# D3R910.net
KiCad netlist of a schematic drawn in Altium Designer
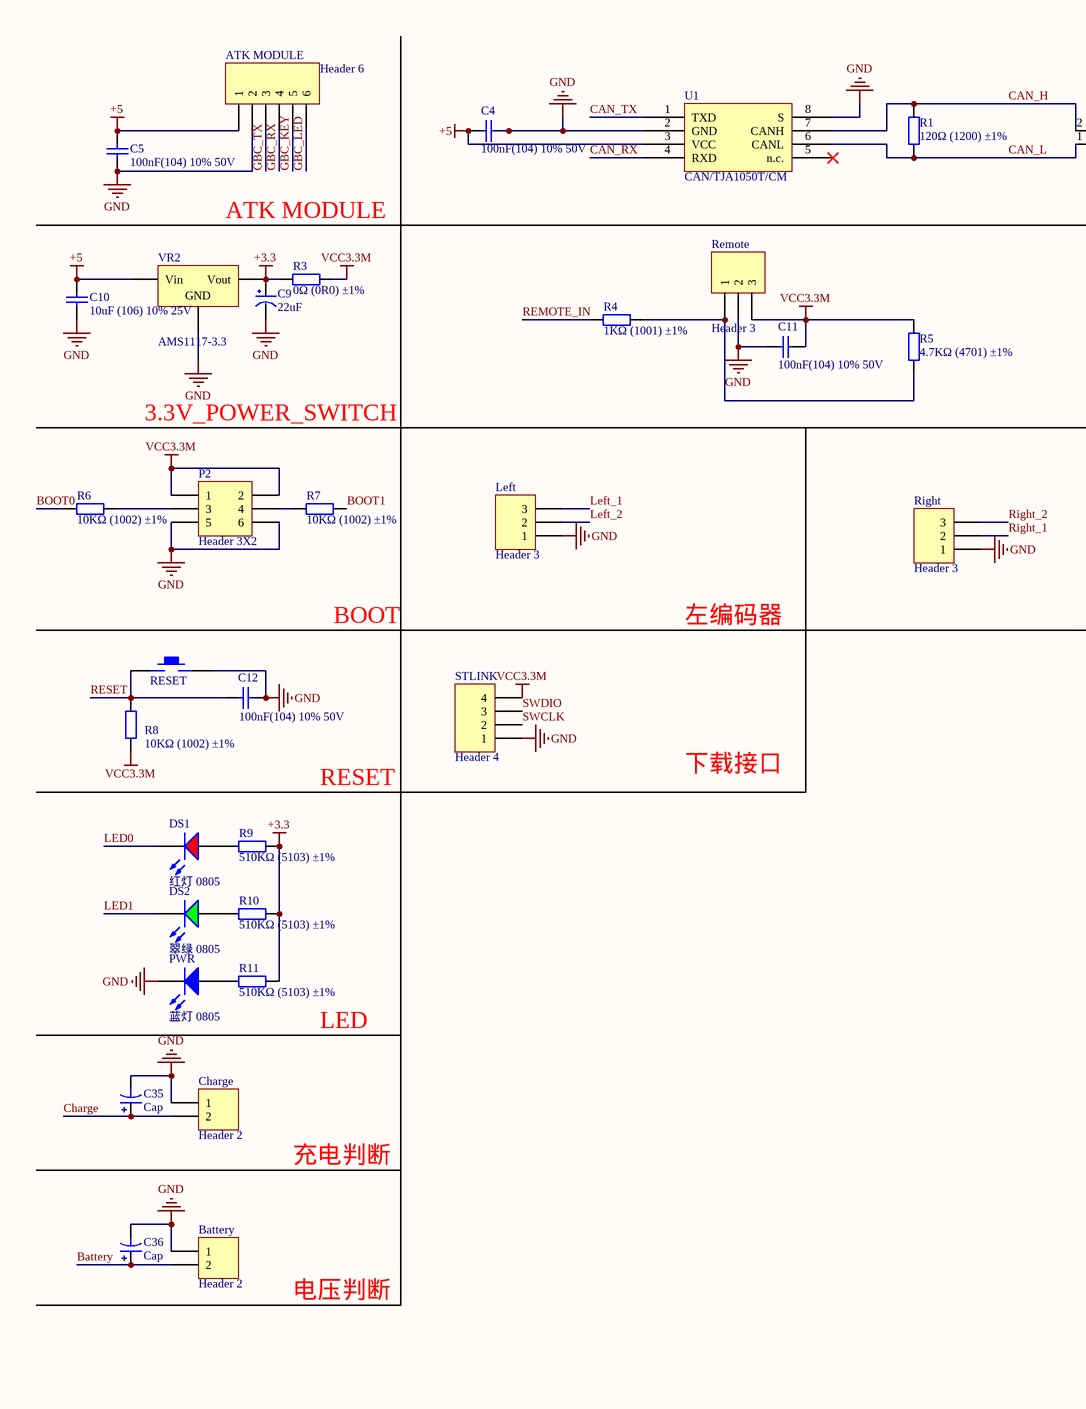
[diagram p0: D3R910.SchDoc, left]
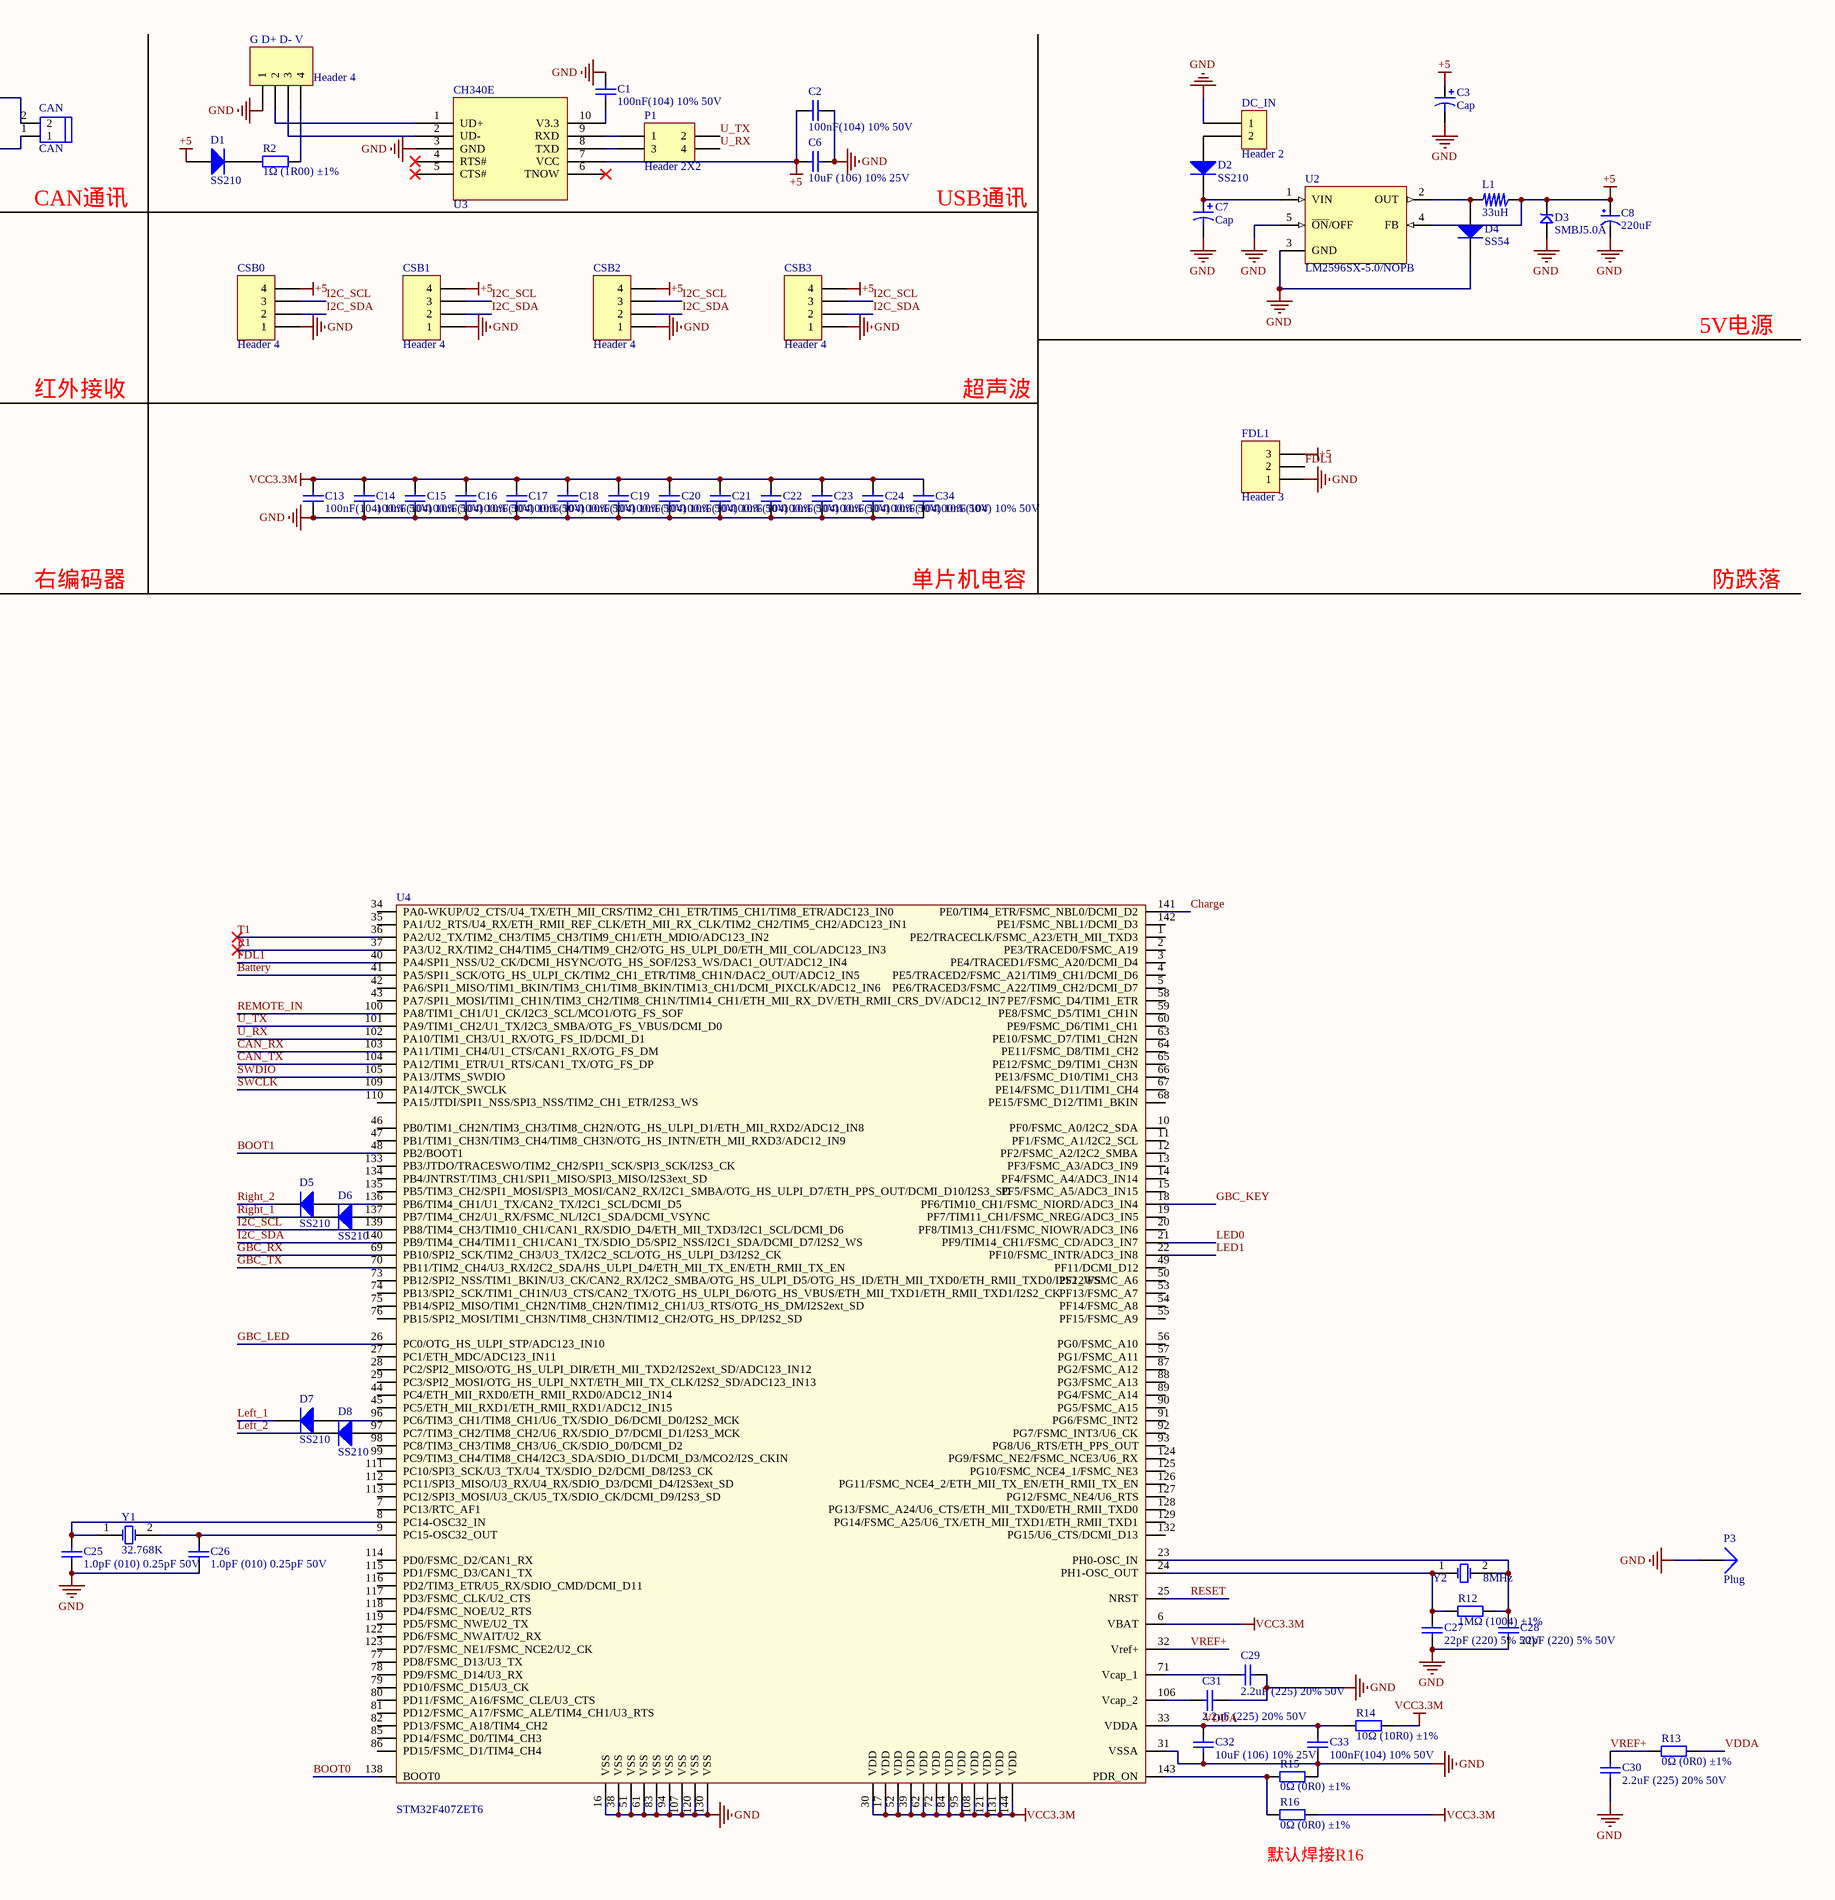
[diagram p1: D3R910.SchDoc, right]

(export (version "E")
  (design (tool "Eeschema 10.0.6"))
  (components
    (comp (ref "ATK MODULE")
      (value "Header 6")
      (footprint "HDR1X6")
      (description "Header, 6-Pin")
      (fields (field (name "PUBLISHER") "Altium Limited"))
      (libsource (lib "Miscellaneous Connectors") (part "Header 6"))
    )
    (comp (ref "Battery")
      (value "Header 2")
      (footprint "HDR1X2")
      (description "Header, 2-Pin")
      (fields (field (name "PUBLISHER") "Altium Limited"))
      (libsource (lib "Miscellaneous Connectors") (part "Header 2"))
    )
    (comp (ref "C1")
      (value "100nF(104) 10% 50V")
      (footprint "LC-0805_C")
      (description "贴片电容")
      (libsource (lib "Miscellaneous Devices LC") (part "0805 100nF(104) 10% 50V"))
    )
    (comp (ref "C2")
      (value "100nF(104) 10% 50V")
      (footprint "LC-0805_C")
      (description "贴片电容")
      (libsource (lib "Miscellaneous Devices LC") (part "0805 100nF(104) 10% 50V"))
    )
    (comp (ref "C3")
      (value "Cap")
      (footprint "CAP-DIP-3.5")
      (description "Cap_DIP")
      (libsource (lib "AD_Chip_Y") (part "Cap_DIP"))
    )
    (comp (ref "C4")
      (value "100nF(104) 10% 50V")
      (footprint "LC-0805_C")
      (description "贴片电容")
      (libsource (lib "Miscellaneous Devices LC") (part "0805 100nF(104) 10% 50V"))
    )
    (comp (ref "C5")
      (value "100nF(104) 10% 50V")
      (footprint "LC-0805_C")
      (description "贴片电容")
      (libsource (lib "Miscellaneous Devices LC") (part "0805 100nF(104) 10% 50V"))
    )
    (comp (ref "C6")
      (value "10uF (106) 10% 25V")
      (footprint "LC-0805_C")
      (description "贴片电容")
      (libsource (lib "Miscellaneous Devices LC") (part "0805 10uF (106) 10% 25V"))
    )
    (comp (ref "C7")
      (value "Cap")
      (footprint "CAP-DIP-3.5")
      (description "Cap_DIP")
      (libsource (lib "AD_Chip_Y") (part "Cap_DIP"))
    )
    (comp (ref "C8")
      (value "220uF")
      (footprint "CC6.56.5")
      (libsource (lib "Explorer STM32F407封装库") (part "CAP"))
    )
    (comp (ref "C9")
      (value "22uF")
      (footprint "CC6.56.5")
      (libsource (lib "Explorer STM32F407封装库") (part "CAP"))
    )
    (comp (ref "C10")
      (value "10uF (106) 10% 25V")
      (footprint "LC-0805_C")
      (description "贴片电容")
      (libsource (lib "Miscellaneous Devices LC") (part "0805 10uF (106) 10% 25V"))
    )
    (comp (ref "C11")
      (value "100nF(104) 10% 50V")
      (footprint "LC-0805_C")
      (description "贴片电容")
      (libsource (lib "Miscellaneous Devices LC") (part "0805 100nF(104) 10% 50V"))
    )
    (comp (ref "C12")
      (value "100nF(104) 10% 50V")
      (footprint "LC-0805_C")
      (description "贴片电容")
      (libsource (lib "Miscellaneous Devices LC") (part "0805 100nF(104) 10% 50V"))
    )
    (comp (ref "C13")
      (value "100nF(104) 10% 50V")
      (footprint "LC-0805_C")
      (description "贴片电容")
      (libsource (lib "Miscellaneous Devices LC") (part "0805 100nF(104) 10% 50V"))
    )
    (comp (ref "C14")
      (value "100nF(104) 10% 50V")
      (footprint "LC-0805_C")
      (description "贴片电容")
      (libsource (lib "Miscellaneous Devices LC") (part "0805 100nF(104) 10% 50V"))
    )
    (comp (ref "C15")
      (value "100nF(104) 10% 50V")
      (footprint "LC-0805_C")
      (description "贴片电容")
      (libsource (lib "Miscellaneous Devices LC") (part "0805 100nF(104) 10% 50V"))
    )
    (comp (ref "C16")
      (value "100nF(104) 10% 50V")
      (footprint "LC-0805_C")
      (description "贴片电容")
      (libsource (lib "Miscellaneous Devices LC") (part "0805 100nF(104) 10% 50V"))
    )
    (comp (ref "C17")
      (value "100nF(104) 10% 50V")
      (footprint "LC-0805_C")
      (description "贴片电容")
      (libsource (lib "Miscellaneous Devices LC") (part "0805 100nF(104) 10% 50V"))
    )
    (comp (ref "C18")
      (value "100nF(104) 10% 50V")
      (footprint "LC-0805_C")
      (description "贴片电容")
      (libsource (lib "Miscellaneous Devices LC") (part "0805 100nF(104) 10% 50V"))
    )
    (comp (ref "C19")
      (value "100nF(104) 10% 50V")
      (footprint "LC-0805_C")
      (description "贴片电容")
      (libsource (lib "Miscellaneous Devices LC") (part "0805 100nF(104) 10% 50V"))
    )
    (comp (ref "C20")
      (value "100nF(104) 10% 50V")
      (footprint "LC-0805_C")
      (description "贴片电容")
      (libsource (lib "Miscellaneous Devices LC") (part "0805 100nF(104) 10% 50V"))
    )
    (comp (ref "C21")
      (value "100nF(104) 10% 50V")
      (footprint "LC-0805_C")
      (description "贴片电容")
      (libsource (lib "Miscellaneous Devices LC") (part "0805 100nF(104) 10% 50V"))
    )
    (comp (ref "C22")
      (value "100nF(104) 10% 50V")
      (footprint "LC-0805_C")
      (description "贴片电容")
      (libsource (lib "Miscellaneous Devices LC") (part "0805 100nF(104) 10% 50V"))
    )
    (comp (ref "C23")
      (value "100nF(104) 10% 50V")
      (footprint "LC-0805_C")
      (description "贴片电容")
      (libsource (lib "Miscellaneous Devices LC") (part "0805 100nF(104) 10% 50V"))
    )
    (comp (ref "C24")
      (value "100nF(104) 10% 50V")
      (footprint "LC-0805_C")
      (description "贴片电容")
      (libsource (lib "Miscellaneous Devices LC") (part "0805 100nF(104) 10% 50V"))
    )
    (comp (ref "C25")
      (value "1.0pF (010) 0.25pF 50V")
      (footprint "LC-0805_C")
      (description "贴片电容")
      (libsource (lib "Miscellaneous Devices LC") (part "0805 1.0pF (010) 0.25pF 50V"))
    )
    (comp (ref "C26")
      (value "1.0pF (010) 0.25pF 50V")
      (footprint "LC-0805_C")
      (description "贴片电容")
      (libsource (lib "Miscellaneous Devices LC") (part "0805 1.0pF (010) 0.25pF 50V"))
    )
    (comp (ref "C27")
      (value "22pF (220) 5% 50V")
      (footprint "LC-0805_C")
      (description "贴片电容")
      (libsource (lib "Miscellaneous Devices LC") (part "0805 22pF (220) 5% 50V"))
    )
    (comp (ref "C28")
      (value "22pF (220) 5% 50V")
      (footprint "LC-0805_C")
      (description "贴片电容")
      (libsource (lib "Miscellaneous Devices LC") (part "0805 22pF (220) 5% 50V"))
    )
    (comp (ref "C29")
      (value "2.2uF (225) 20% 50V")
      (footprint "LC-0805_C")
      (description "贴片电容")
      (libsource (lib "Miscellaneous Devices LC") (part "0805 2.2uF (225) 20% 50V"))
    )
    (comp (ref "C30")
      (value "2.2uF (225) 20% 50V")
      (footprint "LC-0805_C")
      (description "贴片电容")
      (libsource (lib "Miscellaneous Devices LC") (part "0805 2.2uF (225) 20% 50V"))
    )
    (comp (ref "C31")
      (value "2.2uF (225) 20% 50V")
      (footprint "LC-0805_C")
      (description "贴片电容")
      (libsource (lib "Miscellaneous Devices LC") (part "0805 2.2uF (225) 20% 50V"))
    )
    (comp (ref "C32")
      (value "10uF (106) 10% 25V")
      (footprint "LC-0805_C")
      (description "贴片电容")
      (libsource (lib "Miscellaneous Devices LC") (part "0805 10uF (106) 10% 25V"))
    )
    (comp (ref "C33")
      (value "100nF(104) 10% 50V")
      (footprint "LC-0805_C")
      (description "贴片电容")
      (libsource (lib "Miscellaneous Devices LC") (part "0805 100nF(104) 10% 50V"))
    )
    (comp (ref "C34")
      (value "100nF(104) 10% 50V")
      (footprint "LC-0805_C")
      (description "贴片电容")
      (libsource (lib "Miscellaneous Devices LC") (part "0805 100nF(104) 10% 50V"))
    )
    (comp (ref "C35")
      (value "Cap")
      (footprint "CAP-DIP-3.5")
      (description "Cap_DIP")
      (libsource (lib "AD_Chip_Y") (part "Cap_DIP"))
    )
    (comp (ref "C36")
      (value "Cap")
      (footprint "CAP-DIP-3.5")
      (description "Cap_DIP")
      (libsource (lib "AD_Chip_Y") (part "Cap_DIP"))
    )
    (comp (ref "CAN")
      (value "CAN")
      (footprint "HEAD2L-0.8")
      (libsource (lib "Explorer STM32F407封装库") (part "HEAD2"))
    )
    (comp (ref "Charge")
      (value "Header 2")
      (footprint "HDR1X2")
      (description "Header, 2-Pin")
      (fields (field (name "PUBLISHER") "Altium Limited"))
      (libsource (lib "Miscellaneous Connectors") (part "Header 2"))
    )
    (comp (ref "CSB0")
      (value "Header 4")
      (footprint "HDR1X4")
      (description "Header, 4-Pin")
      (fields (field (name "PUBLISHER") "Altium Limited"))
      (libsource (lib "Miscellaneous Connectors") (part "Header 4"))
    )
    (comp (ref "CSB1")
      (value "Header 4")
      (footprint "HDR1X4")
      (description "Header, 4-Pin")
      (fields (field (name "PUBLISHER") "Altium Limited"))
      (libsource (lib "Miscellaneous Connectors") (part "Header 4"))
    )
    (comp (ref "CSB2")
      (value "Header 4")
      (footprint "HDR1X4")
      (description "Header, 4-Pin")
      (fields (field (name "PUBLISHER") "Altium Limited"))
      (libsource (lib "Miscellaneous Connectors") (part "Header 4"))
    )
    (comp (ref "CSB3")
      (value "Header 4")
      (footprint "HDR1X4")
      (description "Header, 4-Pin")
      (fields (field (name "PUBLISHER") "Altium Limited"))
      (libsource (lib "Miscellaneous Connectors") (part "Header 4"))
    )
    (comp (ref "D1")
      (value "SS210")
      (footprint "LC-SMA(DO-214AC)_S1")
      (description "二极管")
      (libsource (lib "Miscellaneous Devices LC") (part "SMA(DO-214AC) SS210"))
    )
    (comp (ref "D2")
      (value "SS210")
      (footprint "LC-SMA(DO-214AC)_S1")
      (description "二极管")
      (libsource (lib "Miscellaneous Devices LC") (part "SMA(DO-214AC) SS210"))
    )
    (comp (ref "D3")
      (value "SMBJ5.0A")
      (footprint "SMBJ")
      (description "TVS")
      (libsource (lib "Explorer STM32F407封装库") (part "SMBJ"))
    )
    (comp (ref "D4")
      (value "SS54")
      (footprint "LC-SMA(DO-214AC)_S1")
      (description "二极管")
      (libsource (lib "Miscellaneous Devices LC") (part "SMA(DO-214AC) SS54"))
    )
    (comp (ref "D5")
      (value "SS210")
      (footprint "LC-SMA(DO-214AC)_S1")
      (description "二极管")
      (libsource (lib "Miscellaneous Devices LC") (part "SMA(DO-214AC) SS210"))
    )
    (comp (ref "D6")
      (value "SS210")
      (footprint "LC-SMA(DO-214AC)_S1")
      (description "二极管")
      (libsource (lib "Miscellaneous Devices LC") (part "SMA(DO-214AC) SS210"))
    )
    (comp (ref "D7")
      (value "SS210")
      (footprint "LC-SMA(DO-214AC)_S1")
      (description "二极管")
      (libsource (lib "Miscellaneous Devices LC") (part "SMA(DO-214AC) SS210"))
    )
    (comp (ref "D8")
      (value "SS210")
      (footprint "LC-SMA(DO-214AC)_S1")
      (description "二极管")
      (libsource (lib "Miscellaneous Devices LC") (part "SMA(DO-214AC) SS210"))
    )
    (comp (ref "DC_IN")
      (value "Header 2")
      (footprint "VH-2A - Circle Hole")
      (description "贴片2p座")
      (libsource (lib "AD_Chip_Y") (part "Header 2"))
    )
    (comp (ref "DS1")
      (value "红灯 0805")
      (footprint "LC-0805_LED_S1")
      (description "发光二极管")
      (libsource (lib "Miscellaneous Devices LC") (part "0805 红灯"))
    )
    (comp (ref "DS2")
      (value "翠绿 0805")
      (footprint "LC-0805_LED_S1")
      (description "发光二极管")
      (libsource (lib "Miscellaneous Devices LC") (part "0805 翠绿"))
    )
    (comp (ref "FDL1")
      (value "Header 3")
      (footprint "HDR1X3")
      (description "Header, 3-Pin")
      (fields (field (name "PUBLISHER") "Altium Limited"))
      (libsource (lib "") (part "Header 3_1"))
    )
    (comp (ref "G D+ D- V")
      (value "Header 4")
      (footprint "HDR1X4")
      (description "Header, 4-Pin")
      (fields (field (name "PUBLISHER") "Altium Limited"))
      (libsource (lib "") (part "Header 4_1"))
    )
    (comp (ref "L1")
      (value "33uH")
      (footprint "L_SOP74")
      (libsource (lib "Explorer STM32F407封装库") (part "L_SOP"))
    )
    (comp (ref "Left")
      (value "Header 3")
      (footprint "HDR1X3")
      (description "Header, 3-Pin")
      (fields (field (name "PUBLISHER") "Altium Limited"))
      (libsource (lib "") (part "Header 3_1"))
    )
    (comp (ref "P1")
      (value "Header 2X2")
      (footprint "HDR2X2")
      (description "Header, 2-Pin, Dual row")
      (fields (field (name "PUBLISHER") "Altium Limited"))
      (libsource (lib "Miscellaneous Connectors") (part "Header 2X2"))
    )
    (comp (ref "P2")
      (value "Header 3X2")
      (footprint "HDR2X3")
      (description "Header, 3-Pin, Dual row")
      (fields (field (name "PUBLISHER") "Altium Limited"))
      (libsource (lib "Miscellaneous Connectors") (part "Header 3X2"))
    )
    (comp (ref "P3")
      (value "Plug")
      (footprint "PIN1")
      (fields (field (name "PUBLISHER") "Altium Limited"))
      (libsource (lib "Miscellaneous Connectors") (part "Plug"))
    )
    (comp (ref "PWR")
      (value "蓝灯 0805")
      (footprint "LC-0805_LED_S1")
      (description "发光二极管")
      (libsource (lib "Miscellaneous Devices LC") (part "0805 蓝灯"))
    )
    (comp (ref "R1")
      (value "120Ω (1200) ±1%")
      (footprint "LC-0805_R")
      (description "贴片电阻")
      (libsource (lib "Miscellaneous Devices LC") (part "0805 120Ω (1200) 1%"))
    )
    (comp (ref "R2")
      (value "1Ω (1R00) ±1%")
      (footprint "LC-0603_R")
      (description "贴片电阻")
      (libsource (lib "Miscellaneous Devices LC") (part "0603 1Ω (1R00) 1%"))
    )
    (comp (ref "R3")
      (value "0Ω (0R0) ±1%")
      (footprint "LC-0603_R")
      (description "贴片电阻")
      (libsource (lib "Miscellaneous Devices LC") (part "0603 0Ω (0R0) 1%"))
    )
    (comp (ref "R4")
      (value "1KΩ (1001) ±1%")
      (footprint "LC-0805_R")
      (description "贴片电阻")
      (libsource (lib "Miscellaneous Devices LC") (part "0805 1KΩ (1001) 1%"))
    )
    (comp (ref "R5")
      (value "4.7KΩ (4701) ±1%")
      (footprint "LC-0805_R")
      (description "贴片电阻")
      (libsource (lib "Miscellaneous Devices LC") (part "0805 4.7KΩ (4701) 1%"))
    )
    (comp (ref "R6")
      (value "10KΩ (1002) ±1%")
      (footprint "LC-0805_R")
      (description "贴片电阻")
      (libsource (lib "") (part "0805 10KΩ (1002) 1%_1"))
    )
    (comp (ref "R7")
      (value "10KΩ (1002) ±1%")
      (footprint "LC-0805_R")
      (description "贴片电阻")
      (libsource (lib "") (part "0805 10KΩ (1002) 1%_1"))
    )
    (comp (ref "R8")
      (value "10KΩ (1002) ±1%")
      (footprint "LC-0805_R")
      (description "贴片电阻")
      (libsource (lib "Miscellaneous Devices LC") (part "0805 10KΩ (1002) 1%"))
    )
    (comp (ref "R9")
      (value "510KΩ (5103) ±1%")
      (footprint "LC-0805_R")
      (description "贴片电阻")
      (libsource (lib "Miscellaneous Devices LC") (part "0805 510KΩ (5103) 1%"))
    )
    (comp (ref "R10")
      (value "510KΩ (5103) ±1%")
      (footprint "LC-0805_R")
      (description "贴片电阻")
      (libsource (lib "Miscellaneous Devices LC") (part "0805 510KΩ (5103) 1%"))
    )
    (comp (ref "R11")
      (value "510KΩ (5103) ±1%")
      (footprint "LC-0805_R")
      (description "贴片电阻")
      (libsource (lib "Miscellaneous Devices LC") (part "0805 510KΩ (5103) 1%"))
    )
    (comp (ref "R12")
      (value "1MΩ (1004) ±1%")
      (footprint "LC-0805_R")
      (description "贴片电阻")
      (libsource (lib "Miscellaneous Devices LC") (part "0805 1MΩ (1004) 1%"))
    )
    (comp (ref "R13")
      (value "0Ω (0R0) ±1%")
      (footprint "LC-0603_R")
      (description "贴片电阻")
      (libsource (lib "Miscellaneous Devices LC") (part "0603 0Ω (0R0) 1%"))
    )
    (comp (ref "R14")
      (value "10Ω (10R0) ±1%")
      (footprint "LC-0805_R")
      (description "贴片电阻")
      (libsource (lib "Miscellaneous Devices LC") (part "0805 10Ω (10R0) 1%"))
    )
    (comp (ref "R15")
      (value "0Ω (0R0) ±1%")
      (footprint "LC-0603_R")
      (description "贴片电阻")
      (libsource (lib "Miscellaneous Devices LC") (part "0603 0Ω (0R0) 1%"))
    )
    (comp (ref "R16")
      (value "0Ω (0R0) ±1%")
      (footprint "LC-0603_R")
      (description "贴片电阻")
      (libsource (lib "Miscellaneous Devices LC") (part "0603 0Ω (0R0) 1%"))
    )
    (comp (ref "Remote")
      (value "Header 3")
      (footprint "HDR1X3")
      (description "Header, 3-Pin")
      (fields (field (name "PUBLISHER") "Altium Limited"))
      (libsource (lib "Miscellaneous Connectors") (part "Header 3"))
    )
    (comp (ref "RESET")
      (value "KEY_M")
      (footprint "KEY_M")
      (libsource (lib "Explorer STM32F407封装库") (part "KEY_M"))
    )
    (comp (ref "Right")
      (value "Header 3")
      (footprint "HDR1X3")
      (description "Header, 3-Pin")
      (fields (field (name "PUBLISHER") "Altium Limited"))
      (libsource (lib "") (part "Header 3_1"))
    )
    (comp (ref "STLINK")
      (value "Header 4")
      (footprint "HDR1X4")
      (description "Header, 4-Pin")
      (fields (field (name "PUBLISHER") "Altium Limited"))
      (libsource (lib "Miscellaneous Connectors") (part "Header 4"))
    )
    (comp (ref "U1")
      (value "CAN/TJA1050T/CM")
      (footprint "LC-SOIC-8_150mil")
      (description "CAN")
      (libsource (lib "Miscellaneous Devices LC") (part "CAN/TJA1050T/CM"))
    )
    (comp (ref "U2")
      (value "LM2596SX-5.0/NOPB")
      (footprint "LC-TO-263-5")
      (description "DC-DC芯片")
      (libsource (lib "Miscellaneous Devices LC") (part "LM2596SX-5.0/NOPB"))
    )
    (comp (ref "U3")
      (value "CH340E")
      (footprint "LC-MSOP-10")
      (description "USB")
      (libsource (lib "AD_Chip_Y") (part "CH340E"))
    )
    (comp (ref "U4")
      (value "STM32F407ZET6")
      (footprint "LQFP144")
      (libsource (lib "Explorer STM32F407封装库") (part "STM32F407ZET6"))
    )
    (comp (ref "VR2")
      (value "AMS1117-3.3")
      (footprint "LC-SOT-223")
      (description "低压差线性稳压(LDO)")
      (libsource (lib "Miscellaneous Devices LC") (part "SOT-223 AMS1117-3.3"))
    )
    (comp (ref "Y1")
      (value "32.768K")
      (footprint "R38")
      (description "Crystal Oscillator")
      (fields (field (name "PUBLISHER") "Altium Limited"))
      (libsource (lib "Miscellaneous Devices") (part "XTAL"))
    )
    (comp (ref "Y2")
      (value "8MHz")
      (footprint "XTAL_US")
      (description "Crystal Oscillator")
      (fields (field (name "PUBLISHER") "Altium Limited"))
      (libsource (lib "Explorer STM32F407封装库") (part "XTAL"))
    )
  )
  (nets
    (net (code "1") (name "+3.3") (class "Default")
      (node (ref "C9") (pin "1") (pinfunction "VCC_1") (pintype "passive"))
      (node (ref "R10") (pin "2") (pinfunction "2_2") (pintype "passive"))
      (node (ref "R11") (pin "2") (pinfunction "2_2") (pintype "passive"))
      (node (ref "R3") (pin "1") (pinfunction "1_1") (pintype "passive"))
      (node (ref "R9") (pin "2") (pinfunction "2_2") (pintype "passive"))
      (node (ref "VR2") (pin "2") (pinfunction "Vout_2") (pintype "passive"))
    )
    (net (code "2") (name "+5") (class "Default")
      (node (ref "ATK MODULE") (pin "1") (pinfunction "1_1") (pintype "passive"))
      (node (ref "C10") (pin "2") (pinfunction "2_2") (pintype "passive"))
      (node (ref "C2") (pin "1") (pinfunction "1_1") (pintype "passive"))
      (node (ref "C3") (pin "1") (pinfunction "1_1") (pintype "passive"))
      (node (ref "C4") (pin "1") (pinfunction "1_1") (pintype "passive"))
      (node (ref "C5") (pin "2") (pinfunction "2_2") (pintype "passive"))
      (node (ref "C6") (pin "1") (pinfunction "1_1") (pintype "passive"))
      (node (ref "C8") (pin "1") (pinfunction "VCC_1") (pintype "passive"))
      (node (ref "CSB0") (pin "4") (pinfunction "4_4") (pintype "passive"))
      (node (ref "CSB1") (pin "4") (pinfunction "4_4") (pintype "passive"))
      (node (ref "CSB2") (pin "4") (pinfunction "4_4") (pintype "passive"))
      (node (ref "CSB3") (pin "4") (pinfunction "4_4") (pintype "passive"))
      (node (ref "D1") (pin "1") (pinfunction "A_1") (pintype "passive"))
      (node (ref "D3") (pin "2") (pintype "passive"))
      (node (ref "FDL1") (pin "3") (pinfunction "3_3") (pintype "passive"))
      (node (ref "L1") (pin "1") (pinfunction "1_1") (pintype "passive"))
      (node (ref "U1") (pin "3") (pinfunction "VCC_3") (pintype "passive"))
      (node (ref "U2") (pin "4") (pinfunction "FB_4") (pintype "input"))
      (node (ref "U3") (pin "7") (pinfunction "VCC_7") (pintype "passive"))
      (node (ref "VR2") (pin "3") (pinfunction "Vin_3") (pintype "passive"))
    )
    (net (code "3") (name "/BOOT0") (class "Default")
      (node (ref "R6") (pin "1") (pinfunction "1_1") (pintype "passive"))
      (node (ref "U4") (pin "138") (pinfunction "BOOT0_138") (pintype "passive"))
    )
    (net (code "4") (name "/BOOT1") (class "Default")
      (node (ref "R7") (pin "2") (pinfunction "2_2") (pintype "passive"))
      (node (ref "U4") (pin "48") (pinfunction "PB2/BOOT1_48") (pintype "passive"))
    )
    (net (code "5") (name "/Battery") (class "Default")
      (node (ref "Battery") (pin "2") (pinfunction "2_2") (pintype "passive"))
      (node (ref "C36") (pin "1") (pinfunction "1_1") (pintype "passive"))
      (node (ref "U4") (pin "41") (pinfunction "PA5/SPI1_SCK/OTG_HS_ULPI_CK/TIM2_CH1_ETR/TIM8_CH1N/DAC2_OUT/ADC12_IN5_41") (pintype "passive"))
    )
    (net (code "6") (name "/CAN_H") (class "Default")
      (node (ref "CAN") (pin "2") (pinfunction "2_2") (pintype "passive"))
      (node (ref "R1") (pin "2") (pinfunction "2_2") (pintype "passive"))
      (node (ref "U1") (pin "7") (pinfunction "CANH_7") (pintype "passive"))
    )
    (net (code "7") (name "/CAN_L") (class "Default")
      (node (ref "CAN") (pin "1") (pinfunction "1_1") (pintype "passive"))
      (node (ref "R1") (pin "1") (pinfunction "1_1") (pintype "passive"))
      (node (ref "U1") (pin "6") (pinfunction "CANL_6") (pintype "passive"))
    )
    (net (code "8") (name "/CAN_RX") (class "Default")
      (node (ref "U1") (pin "4") (pinfunction "RXD_4") (pintype "passive"))
      (node (ref "U4") (pin "103") (pinfunction "PA11/TIM1_CH4/U1_CTS/CAN1_RX/OTG_FS_DM_103") (pintype "passive"))
    )
    (net (code "9") (name "/CAN_TX") (class "Default")
      (node (ref "U1") (pin "1") (pinfunction "TXD_1") (pintype "passive"))
      (node (ref "U4") (pin "104") (pinfunction "PA12/TIM1_ETR/U1_RTS/CAN1_TX/OTG_FS_DP_104") (pintype "passive"))
    )
    (net (code "10") (name "/Charge") (class "Default")
      (node (ref "C35") (pin "1") (pinfunction "1_1") (pintype "passive"))
      (node (ref "Charge") (pin "2") (pinfunction "2_2") (pintype "passive"))
      (node (ref "U4") (pin "141") (pinfunction "PE0/TIM4_ETR/FSMC_NBL0/DCMI_D2_141") (pintype "passive"))
    )
    (net (code "11") (name "/FDL1") (class "Default")
      (node (ref "FDL1") (pin "2") (pinfunction "2_2") (pintype "passive"))
      (node (ref "U4") (pin "40") (pinfunction "PA4/SPI1_NSS/U2_CK/DCMI_HSYNC/OTG_HS_SOF/I2S3_WS/DAC1_OUT/ADC12_IN4_40") (pintype "passive"))
    )
    (net (code "12") (name "/GBC_KEY") (class "Default")
      (node (ref "ATK MODULE") (pin "5") (pinfunction "5_5") (pintype "passive"))
      (node (ref "U4") (pin "18") (pinfunction "PF6/TIM10_CH1/FSMC_NIORD/ADC3_IN4_18") (pintype "passive"))
    )
    (net (code "13") (name "/GBC_LED") (class "Default")
      (node (ref "ATK MODULE") (pin "6") (pinfunction "6_6") (pintype "passive"))
      (node (ref "U4") (pin "26") (pinfunction "PC0/OTG_HS_ULPI_STP/ADC123_IN10_26") (pintype "passive"))
    )
    (net (code "14") (name "/GBC_RX") (class "Default")
      (node (ref "ATK MODULE") (pin "4") (pinfunction "4_4") (pintype "passive"))
      (node (ref "U4") (pin "69") (pinfunction "PB10/SPI2_SCK/TIM2_CH3/U3_TX/I2C2_SCL/OTG_HS_ULPI_D3/I2S2_CK_69") (pintype "passive"))
    )
    (net (code "15") (name "/GBC_TX") (class "Default")
      (node (ref "ATK MODULE") (pin "3") (pinfunction "3_3") (pintype "passive"))
      (node (ref "U4") (pin "70") (pinfunction "PB11/TIM2_CH4/U3_RX/I2C2_SDA/HS_ULPI_D4/ETH_MII_TX_EN/ETH_RMII_TX_EN_70") (pintype "passive"))
    )
    (net (code "16") (name "/I2C_SCL") (class "Default")
      (node (ref "CSB0") (pin "3") (pinfunction "3_3") (pintype "passive"))
      (node (ref "CSB1") (pin "3") (pinfunction "3_3") (pintype "passive"))
      (node (ref "CSB2") (pin "3") (pinfunction "3_3") (pintype "passive"))
      (node (ref "CSB3") (pin "3") (pinfunction "3_3") (pintype "passive"))
      (node (ref "U4") (pin "139") (pinfunction "PB8/TIM4_CH3/TIM10_CH1/CAN1_RX/SDIO_D4/ETH_MII_TXD3/I2C1_SCL/DCMI_D6_139") (pintype "passive"))
    )
    (net (code "17") (name "/I2C_SDA") (class "Default")
      (node (ref "CSB0") (pin "2") (pinfunction "2_2") (pintype "passive"))
      (node (ref "CSB1") (pin "2") (pinfunction "2_2") (pintype "passive"))
      (node (ref "CSB2") (pin "2") (pinfunction "2_2") (pintype "passive"))
      (node (ref "CSB3") (pin "2") (pinfunction "2_2") (pintype "passive"))
      (node (ref "U4") (pin "140") (pinfunction "PB9/TIM4_CH4/TIM11_CH1/CAN1_TX/SDIO_D5/SPI2_NSS/I2C1_SDA/DCMI_D7/I2S2_WS_140") (pintype "passive"))
    )
    (net (code "18") (name "/LED0") (class "Default")
      (node (ref "DS1") (pin "K") (pinfunction "K_K") (pintype "passive"))
      (node (ref "U4") (pin "21") (pinfunction "PF9/TIM14_CH1/FSMC_CD/ADC3_IN7_21") (pintype "passive"))
    )
    (net (code "19") (name "/LED1") (class "Default")
      (node (ref "DS2") (pin "K") (pinfunction "K_K") (pintype "passive"))
      (node (ref "U4") (pin "22") (pinfunction "PF10/FSMC_INTR/ADC3_IN8_22") (pintype "passive"))
    )
    (net (code "20") (name "/Left_1") (class "Default")
      (node (ref "D7") (pin "2") (pinfunction "K_2") (pintype "passive"))
      (node (ref "Left") (pin "3") (pinfunction "3_3") (pintype "passive"))
    )
    (net (code "21") (name "/Left_2") (class "Default")
      (node (ref "D8") (pin "2") (pinfunction "K_2") (pintype "passive"))
      (node (ref "Left") (pin "2") (pinfunction "2_2") (pintype "passive"))
    )
    (net (code "22") (name "/R1") (class "Default")
      (node (ref "U4") (pin "37") (pinfunction "PA3/U2_RX/TIM2_CH4/TIM5_CH4/TIM9_CH2/OTG_HS_ULPI_D0/ETH_MII_COL/ADC123_IN3_37") (pintype "passive+no_connect"))
    )
    (net (code "23") (name "/REMOTE_IN") (class "Default")
      (node (ref "R4") (pin "1") (pinfunction "1_1") (pintype "passive"))
      (node (ref "U4") (pin "100") (pinfunction "PA8/TIM1_CH1/U1_CK/I2C3_SCL/MCO1/OTG_FS_SOF_100") (pintype "passive"))
    )
    (net (code "24") (name "/RESET") (class "Default")
      (node (ref "C12") (pin "2") (pinfunction "2_2") (pintype "passive"))
      (node (ref "R8") (pin "2") (pinfunction "2_2") (pintype "passive"))
      (node (ref "RESET") (pin "1") (pinfunction "1_1") (pintype "passive"))
      (node (ref "U4") (pin "25") (pinfunction "NRST_25") (pintype "passive"))
    )
    (net (code "25") (name "/Right_1") (class "Default")
      (node (ref "D6") (pin "2") (pinfunction "K_2") (pintype "passive"))
      (node (ref "Right") (pin "2") (pinfunction "2_2") (pintype "passive"))
    )
    (net (code "26") (name "/Right_2") (class "Default")
      (node (ref "D5") (pin "2") (pinfunction "K_2") (pintype "passive"))
      (node (ref "Right") (pin "3") (pinfunction "3_3") (pintype "passive"))
    )
    (net (code "27") (name "/SWCLK") (class "Default")
      (node (ref "STLINK") (pin "2") (pinfunction "2_2") (pintype "passive"))
      (node (ref "U4") (pin "109") (pinfunction "PA14/JTCK_SWCLK_109") (pintype "passive"))
    )
    (net (code "28") (name "/SWDIO") (class "Default")
      (node (ref "STLINK") (pin "3") (pinfunction "3_3") (pintype "passive"))
      (node (ref "U4") (pin "105") (pinfunction "PA13/JTMS_SWDIO_105") (pintype "passive"))
    )
    (net (code "29") (name "/T1") (class "Default")
      (node (ref "U4") (pin "36") (pinfunction "PA2/U2_TX/TIM2_CH3/TIM5_CH3/TIM9_CH1/ETH_MDIO/ADC123_IN2_36") (pintype "passive+no_connect"))
    )
    (net (code "30") (name "/U_RX") (class "Default")
      (node (ref "P1") (pin "4") (pinfunction "4_4") (pintype "passive"))
      (node (ref "U4") (pin "102") (pinfunction "PA10/TIM1_CH3/U1_RX/OTG_FS_ID/DCMI_D1_102") (pintype "passive"))
    )
    (net (code "31") (name "/U_TX") (class "Default")
      (node (ref "P1") (pin "2") (pinfunction "2_2") (pintype "passive"))
      (node (ref "U4") (pin "101") (pinfunction "PA9/TIM1_CH2/U1_TX/I2C3_SMBA/OTG_FS_VBUS/DCMI_D0_101") (pintype "passive"))
    )
    (net (code "32") (name "/VDDA") (class "Default")
      (node (ref "C32") (pin "2") (pinfunction "2_2") (pintype "passive"))
      (node (ref "C33") (pin "2") (pinfunction "2_2") (pintype "passive"))
      (node (ref "R13") (pin "2") (pinfunction "2_2") (pintype "passive"))
      (node (ref "R14") (pin "1") (pinfunction "1_1") (pintype "passive"))
      (node (ref "U4") (pin "33") (pinfunction "VDDA_33") (pintype "passive"))
    )
    (net (code "33") (name "/VREF+") (class "Default")
      (node (ref "C30") (pin "2") (pinfunction "2_2") (pintype "passive"))
      (node (ref "R13") (pin "1") (pinfunction "1_1") (pintype "passive"))
      (node (ref "U4") (pin "32") (pinfunction "Vref+_32") (pintype "passive"))
    )
    (net (code "34") (name "GND") (class "Default")
      (node (ref "ATK MODULE") (pin "2") (pinfunction "2_2") (pintype "passive"))
      (node (ref "Battery") (pin "1") (pinfunction "1_1") (pintype "passive"))
      (node (ref "C1") (pin "2") (pinfunction "2_2") (pintype "passive"))
      (node (ref "C10") (pin "1") (pinfunction "1_1") (pintype "passive"))
      (node (ref "C11") (pin "1") (pinfunction "1_1") (pintype "passive"))
      (node (ref "C12") (pin "1") (pinfunction "1_1") (pintype "passive"))
      (node (ref "C13") (pin "2") (pinfunction "2_2") (pintype "passive"))
      (node (ref "C14") (pin "2") (pinfunction "2_2") (pintype "passive"))
      (node (ref "C15") (pin "2") (pinfunction "2_2") (pintype "passive"))
      (node (ref "C16") (pin "2") (pinfunction "2_2") (pintype "passive"))
      (node (ref "C17") (pin "2") (pinfunction "2_2") (pintype "passive"))
      (node (ref "C18") (pin "2") (pinfunction "2_2") (pintype "passive"))
      (node (ref "C19") (pin "2") (pinfunction "2_2") (pintype "passive"))
      (node (ref "C2") (pin "2") (pinfunction "2_2") (pintype "passive"))
      (node (ref "C20") (pin "2") (pinfunction "2_2") (pintype "passive"))
      (node (ref "C21") (pin "2") (pinfunction "2_2") (pintype "passive"))
      (node (ref "C22") (pin "2") (pinfunction "2_2") (pintype "passive"))
      (node (ref "C23") (pin "2") (pinfunction "2_2") (pintype "passive"))
      (node (ref "C24") (pin "2") (pinfunction "2_2") (pintype "passive"))
      (node (ref "C25") (pin "1") (pinfunction "1_1") (pintype "passive"))
      (node (ref "C26") (pin "1") (pinfunction "1_1") (pintype "passive"))
      (node (ref "C27") (pin "1") (pinfunction "1_1") (pintype "passive"))
      (node (ref "C28") (pin "1") (pinfunction "1_1") (pintype "passive"))
      (node (ref "C29") (pin "2") (pinfunction "2_2") (pintype "passive"))
      (node (ref "C3") (pin "2") (pinfunction "2_2") (pintype "passive"))
      (node (ref "C30") (pin "1") (pinfunction "1_1") (pintype "passive"))
      (node (ref "C31") (pin "2") (pinfunction "2_2") (pintype "passive"))
      (node (ref "C32") (pin "1") (pinfunction "1_1") (pintype "passive"))
      (node (ref "C33") (pin "1") (pinfunction "1_1") (pintype "passive"))
      (node (ref "C34") (pin "2") (pinfunction "2_2") (pintype "passive"))
      (node (ref "C35") (pin "2") (pinfunction "2_2") (pintype "passive"))
      (node (ref "C36") (pin "2") (pinfunction "2_2") (pintype "passive"))
      (node (ref "C4") (pin "2") (pinfunction "2_2") (pintype "passive"))
      (node (ref "C5") (pin "1") (pinfunction "1_1") (pintype "passive"))
      (node (ref "C6") (pin "2") (pinfunction "2_2") (pintype "passive"))
      (node (ref "C7") (pin "2") (pinfunction "2_2") (pintype "passive"))
      (node (ref "C8") (pin "2") (pinfunction "GND_2") (pintype "passive"))
      (node (ref "C9") (pin "2") (pinfunction "GND_2") (pintype "passive"))
      (node (ref "CSB0") (pin "1") (pinfunction "1_1") (pintype "passive"))
      (node (ref "CSB1") (pin "1") (pinfunction "1_1") (pintype "passive"))
      (node (ref "CSB2") (pin "1") (pinfunction "1_1") (pintype "passive"))
      (node (ref "CSB3") (pin "1") (pinfunction "1_1") (pintype "passive"))
      (node (ref "Charge") (pin "1") (pinfunction "1_1") (pintype "passive"))
      (node (ref "D3") (pin "1") (pintype "passive"))
      (node (ref "D4") (pin "2") (pinfunction "K_2") (pintype "passive"))
      (node (ref "DC_IN") (pin "1") (pinfunction "1_1") (pintype "passive"))
      (node (ref "FDL1") (pin "1") (pinfunction "1_1") (pintype "passive"))
      (node (ref "G D+ D- V") (pin "1") (pinfunction "1_1") (pintype "passive"))
      (node (ref "Left") (pin "1") (pinfunction "1_1") (pintype "passive"))
      (node (ref "P2") (pin "5") (pinfunction "5_5") (pintype "passive"))
      (node (ref "P2") (pin "6") (pinfunction "6_6") (pintype "passive"))
      (node (ref "P3") (pin "1") (pinfunction "1_1") (pintype "passive"))
      (node (ref "PWR") (pin "K") (pinfunction "K_K") (pintype "passive"))
      (node (ref "R15") (pin "2") (pinfunction "2_2") (pintype "passive"))
      (node (ref "RESET") (pin "2") (pinfunction "2_2") (pintype "passive"))
      (node (ref "Remote") (pin "2") (pinfunction "2_2") (pintype "passive"))
      (node (ref "Right") (pin "1") (pinfunction "1_1") (pintype "passive"))
      (node (ref "STLINK") (pin "1") (pinfunction "1_1") (pintype "passive"))
      (node (ref "U1") (pin "2") (pinfunction "GND_2") (pintype "passive"))
      (node (ref "U1") (pin "8") (pinfunction "S_8") (pintype "passive"))
      (node (ref "U2") (pin "3") (pinfunction "GND_3") (pintype "power_in"))
      (node (ref "U2") (pin "5") (pinfunction "~{ON}/OFF_5") (pintype "input"))
      (node (ref "U3") (pin "3") (pinfunction "GND_3") (pintype "passive"))
      (node (ref "U4") (pin "107") (pinfunction "VSS_107") (pintype "passive"))
      (node (ref "U4") (pin "120") (pinfunction "VSS_120") (pintype "passive"))
      (node (ref "U4") (pin "130") (pinfunction "VSS_130") (pintype "passive"))
      (node (ref "U4") (pin "16") (pinfunction "VSS_16") (pintype "passive"))
      (node (ref "U4") (pin "31") (pinfunction "VSSA_31") (pintype "passive"))
      (node (ref "U4") (pin "38") (pinfunction "VSS_38") (pintype "passive"))
      (node (ref "U4") (pin "51") (pinfunction "VSS_51") (pintype "passive"))
      (node (ref "U4") (pin "61") (pinfunction "VSS_61") (pintype "passive"))
      (node (ref "U4") (pin "83") (pinfunction "VSS_83") (pintype "passive"))
      (node (ref "U4") (pin "94") (pinfunction "VSS_94") (pintype "passive"))
      (node (ref "VR2") (pin "1") (pinfunction "GND_1") (pintype "passive"))
    )
    (net (code "35") (name "Net-(D1-K)") (class "Default")
      (node (ref "D1") (pin "2") (pinfunction "K_2") (pintype "passive"))
      (node (ref "R2") (pin "1") (pinfunction "1_1") (pintype "passive"))
    )
    (net (code "36") (name "Net-(D2-A)") (class "Default")
      (node (ref "D2") (pin "1") (pinfunction "A_1") (pintype "passive"))
      (node (ref "DC_IN") (pin "2") (pinfunction "2_2") (pintype "passive"))
    )
    (net (code "37") (name "Net-(D2-K)") (class "Default")
      (node (ref "C7") (pin "1") (pinfunction "1_1") (pintype "passive"))
      (node (ref "D2") (pin "2") (pinfunction "K_2") (pintype "passive"))
      (node (ref "U2") (pin "1") (pinfunction "VIN_1") (pintype "input"))
    )
    (net (code "38") (name "Net-(D4-A)") (class "Default")
      (node (ref "D4") (pin "1") (pinfunction "A_1") (pintype "passive"))
      (node (ref "L1") (pin "2") (pinfunction "2_2") (pintype "passive"))
      (node (ref "U2") (pin "2") (pinfunction "OUT_2") (pintype "output"))
    )
    (net (code "39") (name "Net-(D5-A)") (class "Default")
      (node (ref "D5") (pin "1") (pinfunction "A_1") (pintype "passive"))
      (node (ref "U4") (pin "136") (pinfunction "PB6/TIM4_CH1/U1_TX/CAN2_TX/I2C1_SCL/DCMI_D5_136") (pintype "passive"))
    )
    (net (code "40") (name "Net-(D6-A)") (class "Default")
      (node (ref "D6") (pin "1") (pinfunction "A_1") (pintype "passive"))
      (node (ref "U4") (pin "137") (pinfunction "PB7/TIM4_CH2/U1_RX/FSMC_NL/I2C1_SDA/DCMI_VSYNC_137") (pintype "passive"))
    )
    (net (code "41") (name "Net-(D7-A)") (class "Default")
      (node (ref "D7") (pin "1") (pinfunction "A_1") (pintype "passive"))
      (node (ref "U4") (pin "96") (pinfunction "PC6/TIM3_CH1/TIM8_CH1/U6_TX/SDIO_D6/DCMI_D0/I2S2_MCK_96") (pintype "passive"))
    )
    (net (code "42") (name "Net-(D8-A)") (class "Default")
      (node (ref "D8") (pin "1") (pinfunction "A_1") (pintype "passive"))
      (node (ref "U4") (pin "97") (pinfunction "PC7/TIM3_CH2/TIM8_CH2/U6_RX/SDIO_D7/DCMI_D1/I2S3_MCK_97") (pintype "passive"))
    )
    (net (code "43") (name "Net-(DS1-PadA)") (class "Default")
      (node (ref "DS1") (pin "A") (pinfunction "A_A") (pintype "passive"))
      (node (ref "R9") (pin "1") (pinfunction "1_1") (pintype "passive"))
    )
    (net (code "44") (name "Net-(DS2-PadA)") (class "Default")
      (node (ref "DS2") (pin "A") (pinfunction "A_A") (pintype "passive"))
      (node (ref "R10") (pin "1") (pinfunction "1_1") (pintype "passive"))
    )
    (net (code "45") (name "Net-(G D+ D- V-Pad4)") (class "Default")
      (node (ref "G D+ D- V") (pin "4") (pinfunction "4_4") (pintype "passive"))
      (node (ref "R2") (pin "2") (pinfunction "2_2") (pintype "passive"))
    )
    (net (code "46") (name "Net-(P2-Pad3)") (class "Default")
      (node (ref "P2") (pin "3") (pinfunction "3_3") (pintype "passive"))
      (node (ref "R6") (pin "2") (pinfunction "2_2") (pintype "passive"))
    )
    (net (code "47") (name "Net-(P2-Pad4)") (class "Default")
      (node (ref "P2") (pin "4") (pinfunction "4_4") (pintype "passive"))
      (node (ref "R7") (pin "1") (pinfunction "1_1") (pintype "passive"))
    )
    (net (code "48") (name "Net-(PWR-PadA)") (class "Default")
      (node (ref "PWR") (pin "A") (pinfunction "A_A") (pintype "passive"))
      (node (ref "R11") (pin "1") (pinfunction "1_1") (pintype "passive"))
    )
    (net (code "49") (name "Net-(R4-Pad2)") (class "Default")
      (node (ref "R4") (pin "2") (pinfunction "2_2") (pintype "passive"))
      (node (ref "R5") (pin "1") (pinfunction "1_1") (pintype "passive"))
      (node (ref "Remote") (pin "1") (pinfunction "1_1") (pintype "passive"))
    )
    (net (code "50") (name "Net-(U3-RXD)") (class "Default")
      (node (ref "P1") (pin "1") (pinfunction "1_1") (pintype "passive"))
      (node (ref "U3") (pin "9") (pinfunction "RXD_9") (pintype "passive"))
    )
    (net (code "51") (name "Net-(U3-TXD)") (class "Default")
      (node (ref "P1") (pin "3") (pinfunction "3_3") (pintype "passive"))
      (node (ref "U3") (pin "8") (pinfunction "TXD_8") (pintype "passive"))
    )
    (net (code "52") (name "Net-(U3-UD+)") (class "Default")
      (node (ref "G D+ D- V") (pin "2") (pinfunction "2_2") (pintype "passive"))
      (node (ref "U3") (pin "1") (pinfunction "UD+_1") (pintype "passive"))
    )
    (net (code "53") (name "Net-(U3-UD-)") (class "Default")
      (node (ref "G D+ D- V") (pin "3") (pinfunction "3_3") (pintype "passive"))
      (node (ref "U3") (pin "2") (pinfunction "UD-_2") (pintype "passive"))
    )
    (net (code "54") (name "Net-(U3-V3.3)") (class "Default")
      (node (ref "C1") (pin "1") (pinfunction "1_1") (pintype "passive"))
      (node (ref "U3") (pin "10") (pinfunction "V3.3_10") (pintype "passive"))
    )
    (net (code "55") (name "Net-(U4-PC14-OSC32_IN)") (class "Default")
      (node (ref "C25") (pin "2") (pinfunction "2_2") (pintype "passive"))
      (node (ref "U4") (pin "8") (pinfunction "PC14-OSC32_IN_8") (pintype "passive"))
      (node (ref "Y1") (pin "1") (pinfunction "OSC1_1") (pintype "passive"))
    )
    (net (code "56") (name "Net-(U4-PC15-OSC32_OUT)") (class "Default")
      (node (ref "C26") (pin "2") (pinfunction "2_2") (pintype "passive"))
      (node (ref "U4") (pin "9") (pinfunction "PC15-OSC32_OUT_9") (pintype "passive"))
      (node (ref "Y1") (pin "2") (pinfunction "OSC2_2") (pintype "passive"))
    )
    (net (code "57") (name "Net-(U4-PDR_ON)") (class "Default")
      (node (ref "R15") (pin "1") (pinfunction "1_1") (pintype "passive"))
      (node (ref "R16") (pin "1") (pinfunction "1_1") (pintype "passive"))
      (node (ref "U4") (pin "143") (pinfunction "PDR_ON_143") (pintype "passive"))
    )
    (net (code "58") (name "Net-(U4-PH0-OSC_IN)") (class "Default")
      (node (ref "C28") (pin "2") (pinfunction "2_2") (pintype "passive"))
      (node (ref "R12") (pin "2") (pinfunction "2_2") (pintype "passive"))
      (node (ref "U4") (pin "23") (pinfunction "PH0-OSC_IN_23") (pintype "passive"))
      (node (ref "Y2") (pin "2") (pinfunction "OSC2_2") (pintype "passive"))
    )
    (net (code "59") (name "Net-(U4-PH1-OSC_OUT)") (class "Default")
      (node (ref "C27") (pin "2") (pinfunction "2_2") (pintype "passive"))
      (node (ref "R12") (pin "1") (pinfunction "1_1") (pintype "passive"))
      (node (ref "U4") (pin "24") (pinfunction "PH1-OSC_OUT_24") (pintype "passive"))
      (node (ref "Y2") (pin "1") (pinfunction "OSC1_1") (pintype "passive"))
    )
    (net (code "60") (name "Net-(U4-Vcap_1)") (class "Default")
      (node (ref "C29") (pin "1") (pinfunction "1_1") (pintype "passive"))
      (node (ref "U4") (pin "71") (pinfunction "Vcap_1_71") (pintype "passive"))
    )
    (net (code "61") (name "Net-(U4-Vcap_2)") (class "Default")
      (node (ref "C31") (pin "1") (pinfunction "1_1") (pintype "passive"))
      (node (ref "U4") (pin "106") (pinfunction "Vcap_2_106") (pintype "passive"))
    )
    (net (code "62") (name "VCC3.3M") (class "Default")
      (node (ref "C11") (pin "2") (pinfunction "2_2") (pintype "passive"))
      (node (ref "C13") (pin "1") (pinfunction "1_1") (pintype "passive"))
      (node (ref "C14") (pin "1") (pinfunction "1_1") (pintype "passive"))
      (node (ref "C15") (pin "1") (pinfunction "1_1") (pintype "passive"))
      (node (ref "C16") (pin "1") (pinfunction "1_1") (pintype "passive"))
      (node (ref "C17") (pin "1") (pinfunction "1_1") (pintype "passive"))
      (node (ref "C18") (pin "1") (pinfunction "1_1") (pintype "passive"))
      (node (ref "C19") (pin "1") (pinfunction "1_1") (pintype "passive"))
      (node (ref "C20") (pin "1") (pinfunction "1_1") (pintype "passive"))
      (node (ref "C21") (pin "1") (pinfunction "1_1") (pintype "passive"))
      (node (ref "C22") (pin "1") (pinfunction "1_1") (pintype "passive"))
      (node (ref "C23") (pin "1") (pinfunction "1_1") (pintype "passive"))
      (node (ref "C24") (pin "1") (pinfunction "1_1") (pintype "passive"))
      (node (ref "C34") (pin "1") (pinfunction "1_1") (pintype "passive"))
      (node (ref "P2") (pin "1") (pinfunction "1_1") (pintype "passive"))
      (node (ref "P2") (pin "2") (pinfunction "2_2") (pintype "passive"))
      (node (ref "R14") (pin "2") (pinfunction "2_2") (pintype "passive"))
      (node (ref "R16") (pin "2") (pinfunction "2_2") (pintype "passive"))
      (node (ref "R3") (pin "2") (pinfunction "2_2") (pintype "passive"))
      (node (ref "R5") (pin "2") (pinfunction "2_2") (pintype "passive"))
      (node (ref "R8") (pin "1") (pinfunction "1_1") (pintype "passive"))
      (node (ref "Remote") (pin "3") (pinfunction "3_3") (pintype "passive"))
      (node (ref "STLINK") (pin "4") (pinfunction "4_4") (pintype "passive"))
      (node (ref "U4") (pin "108") (pinfunction "VDD_108") (pintype "passive"))
      (node (ref "U4") (pin "121") (pinfunction "VDD_121") (pintype "passive"))
      (node (ref "U4") (pin "131") (pinfunction "VDD_131") (pintype "passive"))
      (node (ref "U4") (pin "144") (pinfunction "VDD_144") (pintype "passive"))
      (node (ref "U4") (pin "17") (pinfunction "VDD_17") (pintype "passive"))
      (node (ref "U4") (pin "30") (pinfunction "VDD_30") (pintype "passive"))
      (node (ref "U4") (pin "39") (pinfunction "VDD_39") (pintype "passive"))
      (node (ref "U4") (pin "52") (pinfunction "VDD_52") (pintype "passive"))
      (node (ref "U4") (pin "6") (pinfunction "VBAT_6") (pintype "passive"))
      (node (ref "U4") (pin "62") (pinfunction "VDD_62") (pintype "passive"))
      (node (ref "U4") (pin "72") (pinfunction "VDD_72") (pintype "passive"))
      (node (ref "U4") (pin "84") (pinfunction "VDD_84") (pintype "passive"))
      (node (ref "U4") (pin "95") (pinfunction "VDD_95") (pintype "passive"))
    )
    (net (code "63") (name "unconnected-(U1-n.c.-Pad5)") (class "Default")
      (node (ref "U1") (pin "5") (pinfunction "n.c._5") (pintype "passive+no_connect"))
    )
    (net (code "64") (name "unconnected-(U3-CTS#-Pad5)") (class "Default")
      (node (ref "U3") (pin "5") (pinfunction "CTS#_5") (pintype "passive+no_connect"))
    )
    (net (code "65") (name "unconnected-(U3-RTS#-Pad4)") (class "Default")
      (node (ref "U3") (pin "4") (pinfunction "RTS#_4") (pintype "passive+no_connect"))
    )
    (net (code "66") (name "unconnected-(U3-TNOW-Pad6)") (class "Default")
      (node (ref "U3") (pin "6") (pinfunction "TNOW_6") (pintype "passive+no_connect"))
    )
    (net (code "67") (name "unconnected-(U4-PA0-WKUP{slash}U2_CTS{slash}U4_TX{slash}ETH_MII_CRS{slash}TIM2_CH1_ETR{slash}TIM5_CH1{slash}TIM8_ETR{slash}ADC123_IN0-Pad34)") (class "Default")
      (node (ref "U4") (pin "34") (pinfunction "PA0-WKUP/U2_CTS/U4_TX/ETH_MII_CRS/TIM2_CH1_ETR/TIM5_CH1/TIM8_ETR/ADC123_IN0_34") (pintype "passive"))
    )
    (net (code "68") (name "unconnected-(U4-PA1{slash}U2_RTS{slash}U4_RX{slash}ETH_RMII_REF_CLK{slash}ETH_MII_RX_CLK{slash}TIM2_CH2{slash}TIM5_CH2{slash}ADC123_IN1-Pad35)") (class "Default")
      (node (ref "U4") (pin "35") (pinfunction "PA1/U2_RTS/U4_RX/ETH_RMII_REF_CLK/ETH_MII_RX_CLK/TIM2_CH2/TIM5_CH2/ADC123_IN1_35") (pintype "passive"))
    )
    (net (code "69") (name "unconnected-(U4-PA6{slash}SPI1_MISO{slash}TIM1_BKIN{slash}TIM3_CH1{slash}TIM8_BKIN{slash}TIM13_CH1{slash}DCMI_PIXCLK{slash}ADC12_IN6-Pad42)") (class "Default")
      (node (ref "U4") (pin "42") (pinfunction "PA6/SPI1_MISO/TIM1_BKIN/TIM3_CH1/TIM8_BKIN/TIM13_CH1/DCMI_PIXCLK/ADC12_IN6_42") (pintype "passive"))
    )
    (net (code "70") (name "unconnected-(U4-PA7{slash}SPI1_MOSI{slash}TIM1_CH1N{slash}TIM3_CH2{slash}TIM8_CH1N{slash}TIM14_CH1{slash}ETH_MII_RX_DV{slash}ETH_RMII_CRS_DV{slash}ADC12_IN7-Pad43)") (class "Default")
      (node (ref "U4") (pin "43") (pinfunction "PA7/SPI1_MOSI/TIM1_CH1N/TIM3_CH2/TIM8_CH1N/TIM14_CH1/ETH_MII_RX_DV/ETH_RMII_CRS_DV/ADC12_IN7_43") (pintype "passive"))
    )
    (net (code "71") (name "unconnected-(U4-PA15{slash}JTDI{slash}SPI1_NSS{slash}SPI3_NSS{slash}TIM2_CH1_ETR{slash}I2S3_WS-Pad110)") (class "Default")
      (node (ref "U4") (pin "110") (pinfunction "PA15/JTDI/SPI1_NSS/SPI3_NSS/TIM2_CH1_ETR/I2S3_WS_110") (pintype "passive"))
    )
    (net (code "72") (name "unconnected-(U4-PB0{slash}TIM1_CH2N{slash}TIM3_CH3{slash}TIM8_CH2N{slash}OTG_HS_ULPI_D1{slash}ETH_MII_RXD2{slash}ADC12_IN8-Pad46)") (class "Default")
      (node (ref "U4") (pin "46") (pinfunction "PB0/TIM1_CH2N/TIM3_CH3/TIM8_CH2N/OTG_HS_ULPI_D1/ETH_MII_RXD2/ADC12_IN8_46") (pintype "passive"))
    )
    (net (code "73") (name "unconnected-(U4-PB1{slash}TIM1_CH3N{slash}TIM3_CH4{slash}TIM8_CH3N{slash}OTG_HS_INTN{slash}ETH_MII_RXD3{slash}ADC12_IN9-Pad47)") (class "Default")
      (node (ref "U4") (pin "47") (pinfunction "PB1/TIM1_CH3N/TIM3_CH4/TIM8_CH3N/OTG_HS_INTN/ETH_MII_RXD3/ADC12_IN9_47") (pintype "passive"))
    )
    (net (code "74") (name "unconnected-(U4-PB3{slash}JTDO{slash}TRACESWO{slash}TIM2_CH2{slash}SPI1_SCK{slash}SPI3_SCK{slash}I2S3_CK-Pad133)") (class "Default")
      (node (ref "U4") (pin "133") (pinfunction "PB3/JTDO/TRACESWO/TIM2_CH2/SPI1_SCK/SPI3_SCK/I2S3_CK_133") (pintype "passive"))
    )
    (net (code "75") (name "unconnected-(U4-PB4{slash}JNTRST{slash}TIM3_CH1{slash}SPI1_MISO{slash}SPI3_MISO{slash}I2S3ext_SD-Pad134)") (class "Default")
      (node (ref "U4") (pin "134") (pinfunction "PB4/JNTRST/TIM3_CH1/SPI1_MISO/SPI3_MISO/I2S3ext_SD_134") (pintype "passive"))
    )
    (net (code "76") (name "unconnected-(U4-PB5{slash}TIM3_CH2{slash}SPI1_MOSI{slash}SPI3_MOSI{slash}CAN2_RX{slash}I2C1_SMBA{slash}OTG_HS_ULPI_D7{slash}ETH_PPS_OUT{slash}DCMI_D10{slash}I2S3_SD-Pad135)") (class "Default")
      (node (ref "U4") (pin "135") (pinfunction "PB5/TIM3_CH2/SPI1_MOSI/SPI3_MOSI/CAN2_RX/I2C1_SMBA/OTG_HS_ULPI_D7/ETH_PPS_OUT/DCMI_D10/I2S3_SD_135") (pintype "passive"))
    )
    (net (code "77") (name "unconnected-(U4-PB12{slash}SPI2_NSS{slash}TIM1_BKIN{slash}U3_CK{slash}CAN2_RX{slash}I2C2_SMBA{slash}OTG_HS_ULPI_D5{slash}OTG_HS_ID{slash}ETH_MII_TXD0{slash}ETH_RMII_TXD0{slash}I2S2_WS-Pad73)") (class "Default")
      (node (ref "U4") (pin "73") (pinfunction "PB12/SPI2_NSS/TIM1_BKIN/U3_CK/CAN2_RX/I2C2_SMBA/OTG_HS_ULPI_D5/OTG_HS_ID/ETH_MII_TXD0/ETH_RMII_TXD0/I2S2_WS_73") (pintype "passive"))
    )
    (net (code "78") (name "unconnected-(U4-PB13{slash}SPI2_SCK{slash}TIM1_CH1N{slash}U3_CTS{slash}CAN2_TX{slash}OTG_HS_ULPI_D6{slash}OTG_HS_VBUS{slash}ETH_MII_TXD1{slash}ETH_RMII_TXD1{slash}I2S2_CK-Pad74)") (class "Default")
      (node (ref "U4") (pin "74") (pinfunction "PB13/SPI2_SCK/TIM1_CH1N/U3_CTS/CAN2_TX/OTG_HS_ULPI_D6/OTG_HS_VBUS/ETH_MII_TXD1/ETH_RMII_TXD1/I2S2_CK_74") (pintype "passive"))
    )
    (net (code "79") (name "unconnected-(U4-PB14{slash}SPI2_MISO{slash}TIM1_CH2N{slash}TIM8_CH2N{slash}TIM12_CH1{slash}U3_RTS{slash}OTG_HS_DM{slash}I2S2ext_SD-Pad75)") (class "Default")
      (node (ref "U4") (pin "75") (pinfunction "PB14/SPI2_MISO/TIM1_CH2N/TIM8_CH2N/TIM12_CH1/U3_RTS/OTG_HS_DM/I2S2ext_SD_75") (pintype "passive"))
    )
    (net (code "80") (name "unconnected-(U4-PB15{slash}SPI2_MOSI{slash}TIM1_CH3N{slash}TIM8_CH3N{slash}TIM12_CH2{slash}OTG_HS_DP{slash}I2S2_SD-Pad76)") (class "Default")
      (node (ref "U4") (pin "76") (pinfunction "PB15/SPI2_MOSI/TIM1_CH3N/TIM8_CH3N/TIM12_CH2/OTG_HS_DP/I2S2_SD_76") (pintype "passive"))
    )
    (net (code "81") (name "unconnected-(U4-PC1{slash}ETH_MDC{slash}ADC123_IN11-Pad27)") (class "Default")
      (node (ref "U4") (pin "27") (pinfunction "PC1/ETH_MDC/ADC123_IN11_27") (pintype "passive"))
    )
    (net (code "82") (name "unconnected-(U4-PC2{slash}SPI2_MISO{slash}OTG_HS_ULPI_DIR{slash}ETH_MII_TXD2{slash}I2S2ext_SD{slash}ADC123_IN12-Pad28)") (class "Default")
      (node (ref "U4") (pin "28") (pinfunction "PC2/SPI2_MISO/OTG_HS_ULPI_DIR/ETH_MII_TXD2/I2S2ext_SD/ADC123_IN12_28") (pintype "passive"))
    )
    (net (code "83") (name "unconnected-(U4-PC3{slash}SPI2_MOSI{slash}OTG_HS_ULPI_NXT{slash}ETH_MII_TX_CLK{slash}I2S2_SD{slash}ADC123_IN13-Pad29)") (class "Default")
      (node (ref "U4") (pin "29") (pinfunction "PC3/SPI2_MOSI/OTG_HS_ULPI_NXT/ETH_MII_TX_CLK/I2S2_SD/ADC123_IN13_29") (pintype "passive"))
    )
    (net (code "84") (name "unconnected-(U4-PC4{slash}ETH_MII_RXD0{slash}ETH_RMII_RXD0{slash}ADC12_IN14-Pad44)") (class "Default")
      (node (ref "U4") (pin "44") (pinfunction "PC4/ETH_MII_RXD0/ETH_RMII_RXD0/ADC12_IN14_44") (pintype "passive"))
    )
    (net (code "85") (name "unconnected-(U4-PC5{slash}ETH_MII_RXD1{slash}ETH_RMII_RXD1{slash}ADC12_IN15-Pad45)") (class "Default")
      (node (ref "U4") (pin "45") (pinfunction "PC5/ETH_MII_RXD1/ETH_RMII_RXD1/ADC12_IN15_45") (pintype "passive"))
    )
    (net (code "86") (name "unconnected-(U4-PC8{slash}TIM3_CH3{slash}TIM8_CH3{slash}U6_CK{slash}SDIO_D0{slash}DCMI_D2-Pad98)") (class "Default")
      (node (ref "U4") (pin "98") (pinfunction "PC8/TIM3_CH3/TIM8_CH3/U6_CK/SDIO_D0/DCMI_D2_98") (pintype "passive"))
    )
    (net (code "87") (name "unconnected-(U4-PC9{slash}TIM3_CH4{slash}TIM8_CH4{slash}I2C3_SDA{slash}SDIO_D1{slash}DCMI_D3{slash}MCO2{slash}I2S_CKIN-Pad99)") (class "Default")
      (node (ref "U4") (pin "99") (pinfunction "PC9/TIM3_CH4/TIM8_CH4/I2C3_SDA/SDIO_D1/DCMI_D3/MCO2/I2S_CKIN_99") (pintype "passive"))
    )
    (net (code "88") (name "unconnected-(U4-PC10{slash}SPI3_SCK{slash}U3_TX{slash}U4_TX{slash}SDIO_D2{slash}DCMI_D8{slash}I2S3_CK-Pad111)") (class "Default")
      (node (ref "U4") (pin "111") (pinfunction "PC10/SPI3_SCK/U3_TX/U4_TX/SDIO_D2/DCMI_D8/I2S3_CK_111") (pintype "passive"))
    )
    (net (code "89") (name "unconnected-(U4-PC11{slash}SPI3_MISO{slash}U3_RX{slash}U4_RX{slash}SDIO_D3{slash}DCMI_D4{slash}I2S3ext_SD-Pad112)") (class "Default")
      (node (ref "U4") (pin "112") (pinfunction "PC11/SPI3_MISO/U3_RX/U4_RX/SDIO_D3/DCMI_D4/I2S3ext_SD_112") (pintype "passive"))
    )
    (net (code "90") (name "unconnected-(U4-PC12{slash}SPI3_MOSI{slash}U3_CK{slash}U5_TX{slash}SDIO_CK{slash}DCMI_D9{slash}I2S3_SD-Pad113)") (class "Default")
      (node (ref "U4") (pin "113") (pinfunction "PC12/SPI3_MOSI/U3_CK/U5_TX/SDIO_CK/DCMI_D9/I2S3_SD_113") (pintype "passive"))
    )
    (net (code "91") (name "unconnected-(U4-PC13{slash}RTC_AF1-Pad7)") (class "Default")
      (node (ref "U4") (pin "7") (pinfunction "PC13/RTC_AF1_7") (pintype "passive"))
    )
    (net (code "92") (name "unconnected-(U4-PD0{slash}FSMC_D2{slash}CAN1_RX-Pad114)") (class "Default")
      (node (ref "U4") (pin "114") (pinfunction "PD0/FSMC_D2/CAN1_RX_114") (pintype "passive"))
    )
    (net (code "93") (name "unconnected-(U4-PD1{slash}FSMC_D3{slash}CAN1_TX-Pad115)") (class "Default")
      (node (ref "U4") (pin "115") (pinfunction "PD1/FSMC_D3/CAN1_TX_115") (pintype "passive"))
    )
    (net (code "94") (name "unconnected-(U4-PD2{slash}TIM3_ETR{slash}U5_RX{slash}SDIO_CMD{slash}DCMI_D11-Pad116)") (class "Default")
      (node (ref "U4") (pin "116") (pinfunction "PD2/TIM3_ETR/U5_RX/SDIO_CMD/DCMI_D11_116") (pintype "passive"))
    )
    (net (code "95") (name "unconnected-(U4-PD3{slash}FSMC_CLK{slash}U2_CTS-Pad117)") (class "Default")
      (node (ref "U4") (pin "117") (pinfunction "PD3/FSMC_CLK/U2_CTS_117") (pintype "passive"))
    )
    (net (code "96") (name "unconnected-(U4-PD4{slash}FSMC_NOE{slash}U2_RTS-Pad118)") (class "Default")
      (node (ref "U4") (pin "118") (pinfunction "PD4/FSMC_NOE/U2_RTS_118") (pintype "passive"))
    )
    (net (code "97") (name "unconnected-(U4-PD5{slash}FSMC_NWE{slash}U2_TX-Pad119)") (class "Default")
      (node (ref "U4") (pin "119") (pinfunction "PD5/FSMC_NWE/U2_TX_119") (pintype "passive"))
    )
    (net (code "98") (name "unconnected-(U4-PD6{slash}FSMC_NWAIT{slash}U2_RX-Pad122)") (class "Default")
      (node (ref "U4") (pin "122") (pinfunction "PD6/FSMC_NWAIT/U2_RX_122") (pintype "passive"))
    )
    (net (code "99") (name "unconnected-(U4-PD7{slash}FSMC_NE1{slash}FSMC_NCE2{slash}U2_CK-Pad123)") (class "Default")
      (node (ref "U4") (pin "123") (pinfunction "PD7/FSMC_NE1/FSMC_NCE2/U2_CK_123") (pintype "passive"))
    )
    (net (code "100") (name "unconnected-(U4-PD8{slash}FSMC_D13{slash}U3_TX-Pad77)") (class "Default")
      (node (ref "U4") (pin "77") (pinfunction "PD8/FSMC_D13/U3_TX_77") (pintype "passive"))
    )
    (net (code "101") (name "unconnected-(U4-PD9{slash}FSMC_D14{slash}U3_RX-Pad78)") (class "Default")
      (node (ref "U4") (pin "78") (pinfunction "PD9/FSMC_D14/U3_RX_78") (pintype "passive"))
    )
    (net (code "102") (name "unconnected-(U4-PD10{slash}FSMC_D15{slash}U3_CK-Pad79)") (class "Default")
      (node (ref "U4") (pin "79") (pinfunction "PD10/FSMC_D15/U3_CK_79") (pintype "passive"))
    )
    (net (code "103") (name "unconnected-(U4-PD11{slash}FSMC_A16{slash}FSMC_CLE{slash}U3_CTS-Pad80)") (class "Default")
      (node (ref "U4") (pin "80") (pinfunction "PD11/FSMC_A16/FSMC_CLE/U3_CTS_80") (pintype "passive"))
    )
    (net (code "104") (name "unconnected-(U4-PD12{slash}FSMC_A17{slash}FSMC_ALE{slash}TIM4_CH1{slash}U3_RTS-Pad81)") (class "Default")
      (node (ref "U4") (pin "81") (pinfunction "PD12/FSMC_A17/FSMC_ALE/TIM4_CH1/U3_RTS_81") (pintype "passive"))
    )
    (net (code "105") (name "unconnected-(U4-PD13{slash}FSMC_A18{slash}TIM4_CH2-Pad82)") (class "Default")
      (node (ref "U4") (pin "82") (pinfunction "PD13/FSMC_A18/TIM4_CH2_82") (pintype "passive"))
    )
    (net (code "106") (name "unconnected-(U4-PD14{slash}FSMC_D0{slash}TIM4_CH3-Pad85)") (class "Default")
      (node (ref "U4") (pin "85") (pinfunction "PD14/FSMC_D0/TIM4_CH3_85") (pintype "passive"))
    )
    (net (code "107") (name "unconnected-(U4-PD15{slash}FSMC_D1{slash}TIM4_CH4-Pad86)") (class "Default")
      (node (ref "U4") (pin "86") (pinfunction "PD15/FSMC_D1/TIM4_CH4_86") (pintype "passive"))
    )
    (net (code "108") (name "unconnected-(U4-PE1{slash}FSMC_NBL1{slash}DCMI_D3-Pad142)") (class "Default")
      (node (ref "U4") (pin "142") (pinfunction "PE1/FSMC_NBL1/DCMI_D3_142") (pintype "passive"))
    )
    (net (code "109") (name "unconnected-(U4-PE2{slash}TRACECLK{slash}FSMC_A23{slash}ETH_MII_TXD3-Pad1)") (class "Default")
      (node (ref "U4") (pin "1") (pinfunction "PE2/TRACECLK/FSMC_A23/ETH_MII_TXD3_1") (pintype "passive"))
    )
    (net (code "110") (name "unconnected-(U4-PE3{slash}TRACED0{slash}FSMC_A19-Pad2)") (class "Default")
      (node (ref "U4") (pin "2") (pinfunction "PE3/TRACED0/FSMC_A19_2") (pintype "passive"))
    )
    (net (code "111") (name "unconnected-(U4-PE4{slash}TRACED1{slash}FSMC_A20{slash}DCMI_D4-Pad3)") (class "Default")
      (node (ref "U4") (pin "3") (pinfunction "PE4/TRACED1/FSMC_A20/DCMI_D4_3") (pintype "passive"))
    )
    (net (code "112") (name "unconnected-(U4-PE5{slash}TRACED2{slash}FSMC_A21{slash}TIM9_CH1{slash}DCMI_D6-Pad4)") (class "Default")
      (node (ref "U4") (pin "4") (pinfunction "PE5/TRACED2/FSMC_A21/TIM9_CH1/DCMI_D6_4") (pintype "passive"))
    )
    (net (code "113") (name "unconnected-(U4-PE6{slash}TRACED3{slash}FSMC_A22{slash}TIM9_CH2{slash}DCMI_D7-Pad5)") (class "Default")
      (node (ref "U4") (pin "5") (pinfunction "PE6/TRACED3/FSMC_A22/TIM9_CH2/DCMI_D7_5") (pintype "passive"))
    )
    (net (code "114") (name "unconnected-(U4-PE7{slash}FSMC_D4{slash}TIM1_ETR-Pad58)") (class "Default")
      (node (ref "U4") (pin "58") (pinfunction "PE7/FSMC_D4/TIM1_ETR_58") (pintype "passive"))
    )
    (net (code "115") (name "unconnected-(U4-PE8{slash}FSMC_D5{slash}TIM1_CH1N-Pad59)") (class "Default")
      (node (ref "U4") (pin "59") (pinfunction "PE8/FSMC_D5/TIM1_CH1N_59") (pintype "passive"))
    )
    (net (code "116") (name "unconnected-(U4-PE9{slash}FSMC_D6{slash}TIM1_CH1-Pad60)") (class "Default")
      (node (ref "U4") (pin "60") (pinfunction "PE9/FSMC_D6/TIM1_CH1_60") (pintype "passive"))
    )
    (net (code "117") (name "unconnected-(U4-PE10{slash}FSMC_D7{slash}TIM1_CH2N-Pad63)") (class "Default")
      (node (ref "U4") (pin "63") (pinfunction "PE10/FSMC_D7/TIM1_CH2N_63") (pintype "passive"))
    )
    (net (code "118") (name "unconnected-(U4-PE11{slash}FSMC_D8{slash}TIM1_CH2-Pad64)") (class "Default")
      (node (ref "U4") (pin "64") (pinfunction "PE11/FSMC_D8/TIM1_CH2_64") (pintype "passive"))
    )
    (net (code "119") (name "unconnected-(U4-PE12{slash}FSMC_D9{slash}TIM1_CH3N-Pad65)") (class "Default")
      (node (ref "U4") (pin "65") (pinfunction "PE12/FSMC_D9/TIM1_CH3N_65") (pintype "passive"))
    )
    (net (code "120") (name "unconnected-(U4-PE13{slash}FSMC_D10{slash}TIM1_CH3-Pad66)") (class "Default")
      (node (ref "U4") (pin "66") (pinfunction "PE13/FSMC_D10/TIM1_CH3_66") (pintype "passive"))
    )
    (net (code "121") (name "unconnected-(U4-PE14{slash}FSMC_D11{slash}TIM1_CH4-Pad67)") (class "Default")
      (node (ref "U4") (pin "67") (pinfunction "PE14/FSMC_D11/TIM1_CH4_67") (pintype "passive"))
    )
    (net (code "122") (name "unconnected-(U4-PE15{slash}FSMC_D12{slash}TIM1_BKIN-Pad68)") (class "Default")
      (node (ref "U4") (pin "68") (pinfunction "PE15/FSMC_D12/TIM1_BKIN_68") (pintype "passive"))
    )
    (net (code "123") (name "unconnected-(U4-PF0{slash}FSMC_A0{slash}I2C2_SDA-Pad10)") (class "Default")
      (node (ref "U4") (pin "10") (pinfunction "PF0/FSMC_A0/I2C2_SDA_10") (pintype "passive"))
    )
    (net (code "124") (name "unconnected-(U4-PF1{slash}FSMC_A1{slash}I2C2_SCL-Pad11)") (class "Default")
      (node (ref "U4") (pin "11") (pinfunction "PF1/FSMC_A1/I2C2_SCL_11") (pintype "passive"))
    )
    (net (code "125") (name "unconnected-(U4-PF2{slash}FSMC_A2{slash}I2C2_SMBA-Pad12)") (class "Default")
      (node (ref "U4") (pin "12") (pinfunction "PF2/FSMC_A2/I2C2_SMBA_12") (pintype "passive"))
    )
    (net (code "126") (name "unconnected-(U4-PF3{slash}FSMC_A3{slash}ADC3_IN9-Pad13)") (class "Default")
      (node (ref "U4") (pin "13") (pinfunction "PF3/FSMC_A3/ADC3_IN9_13") (pintype "passive"))
    )
    (net (code "127") (name "unconnected-(U4-PF4{slash}FSMC_A4{slash}ADC3_IN14-Pad14)") (class "Default")
      (node (ref "U4") (pin "14") (pinfunction "PF4/FSMC_A4/ADC3_IN14_14") (pintype "passive"))
    )
    (net (code "128") (name "unconnected-(U4-PF5{slash}FSMC_A5{slash}ADC3_IN15-Pad15)") (class "Default")
      (node (ref "U4") (pin "15") (pinfunction "PF5/FSMC_A5/ADC3_IN15_15") (pintype "passive"))
    )
    (net (code "129") (name "unconnected-(U4-PF7{slash}TIM11_CH1{slash}FSMC_NREG{slash}ADC3_IN5-Pad19)") (class "Default")
      (node (ref "U4") (pin "19") (pinfunction "PF7/TIM11_CH1/FSMC_NREG/ADC3_IN5_19") (pintype "passive"))
    )
    (net (code "130") (name "unconnected-(U4-PF8{slash}TIM13_CH1{slash}FSMC_NIOWR{slash}ADC3_IN6-Pad20)") (class "Default")
      (node (ref "U4") (pin "20") (pinfunction "PF8/TIM13_CH1/FSMC_NIOWR/ADC3_IN6_20") (pintype "passive"))
    )
    (net (code "131") (name "unconnected-(U4-PF11{slash}DCMI_D12-Pad49)") (class "Default")
      (node (ref "U4") (pin "49") (pinfunction "PF11/DCMI_D12_49") (pintype "passive"))
    )
    (net (code "132") (name "unconnected-(U4-PF12{slash}FSMC_A6-Pad50)") (class "Default")
      (node (ref "U4") (pin "50") (pinfunction "PF12/FSMC_A6_50") (pintype "passive"))
    )
    (net (code "133") (name "unconnected-(U4-PF13{slash}FSMC_A7-Pad53)") (class "Default")
      (node (ref "U4") (pin "53") (pinfunction "PF13/FSMC_A7_53") (pintype "passive"))
    )
    (net (code "134") (name "unconnected-(U4-PF14{slash}FSMC_A8-Pad54)") (class "Default")
      (node (ref "U4") (pin "54") (pinfunction "PF14/FSMC_A8_54") (pintype "passive"))
    )
    (net (code "135") (name "unconnected-(U4-PF15{slash}FSMC_A9-Pad55)") (class "Default")
      (node (ref "U4") (pin "55") (pinfunction "PF15/FSMC_A9_55") (pintype "passive"))
    )
    (net (code "136") (name "unconnected-(U4-PG0{slash}FSMC_A10-Pad56)") (class "Default")
      (node (ref "U4") (pin "56") (pinfunction "PG0/FSMC_A10_56") (pintype "passive"))
    )
    (net (code "137") (name "unconnected-(U4-PG1{slash}FSMC_A11-Pad57)") (class "Default")
      (node (ref "U4") (pin "57") (pinfunction "PG1/FSMC_A11_57") (pintype "passive"))
    )
    (net (code "138") (name "unconnected-(U4-PG2{slash}FSMC_A12-Pad87)") (class "Default")
      (node (ref "U4") (pin "87") (pinfunction "PG2/FSMC_A12_87") (pintype "passive"))
    )
    (net (code "139") (name "unconnected-(U4-PG3{slash}FSMC_A13-Pad88)") (class "Default")
      (node (ref "U4") (pin "88") (pinfunction "PG3/FSMC_A13_88") (pintype "passive"))
    )
    (net (code "140") (name "unconnected-(U4-PG4{slash}FSMC_A14-Pad89)") (class "Default")
      (node (ref "U4") (pin "89") (pinfunction "PG4/FSMC_A14_89") (pintype "passive"))
    )
    (net (code "141") (name "unconnected-(U4-PG5{slash}FSMC_A15-Pad90)") (class "Default")
      (node (ref "U4") (pin "90") (pinfunction "PG5/FSMC_A15_90") (pintype "passive"))
    )
    (net (code "142") (name "unconnected-(U4-PG6{slash}FSMC_INT2-Pad91)") (class "Default")
      (node (ref "U4") (pin "91") (pinfunction "PG6/FSMC_INT2_91") (pintype "passive"))
    )
    (net (code "143") (name "unconnected-(U4-PG7{slash}FSMC_INT3{slash}U6_CK-Pad92)") (class "Default")
      (node (ref "U4") (pin "92") (pinfunction "PG7/FSMC_INT3/U6_CK_92") (pintype "passive"))
    )
    (net (code "144") (name "unconnected-(U4-PG8{slash}U6_RTS{slash}ETH_PPS_OUT-Pad93)") (class "Default")
      (node (ref "U4") (pin "93") (pinfunction "PG8/U6_RTS/ETH_PPS_OUT_93") (pintype "passive"))
    )
    (net (code "145") (name "unconnected-(U4-PG9{slash}FSMC_NE2{slash}FSMC_NCE3{slash}U6_RX-Pad124)") (class "Default")
      (node (ref "U4") (pin "124") (pinfunction "PG9/FSMC_NE2/FSMC_NCE3/U6_RX_124") (pintype "passive"))
    )
    (net (code "146") (name "unconnected-(U4-PG10{slash}FSMC_NCE4_1{slash}FSMC_NE3-Pad125)") (class "Default")
      (node (ref "U4") (pin "125") (pinfunction "PG10/FSMC_NCE4_1/FSMC_NE3_125") (pintype "passive"))
    )
    (net (code "147") (name "unconnected-(U4-PG11{slash}FSMC_NCE4_2{slash}ETH_MII_TX_EN{slash}ETH_RMII_TX_EN-Pad126)") (class "Default")
      (node (ref "U4") (pin "126") (pinfunction "PG11/FSMC_NCE4_2/ETH_MII_TX_EN/ETH_RMII_TX_EN_126") (pintype "passive"))
    )
    (net (code "148") (name "unconnected-(U4-PG12{slash}FSMC_NE4{slash}U6_RTS-Pad127)") (class "Default")
      (node (ref "U4") (pin "127") (pinfunction "PG12/FSMC_NE4/U6_RTS_127") (pintype "passive"))
    )
    (net (code "149") (name "unconnected-(U4-PG13{slash}FSMC_A24{slash}U6_CTS{slash}ETH_MII_TXD0{slash}ETH_RMII_TXD0-Pad128)") (class "Default")
      (node (ref "U4") (pin "128") (pinfunction "PG13/FSMC_A24/U6_CTS/ETH_MII_TXD0/ETH_RMII_TXD0_128") (pintype "passive"))
    )
    (net (code "150") (name "unconnected-(U4-PG14{slash}FSMC_A25{slash}U6_TX{slash}ETH_MII_TXD1{slash}ETH_RMII_TXD1-Pad129)") (class "Default")
      (node (ref "U4") (pin "129") (pinfunction "PG14/FSMC_A25/U6_TX/ETH_MII_TXD1/ETH_RMII_TXD1_129") (pintype "passive"))
    )
    (net (code "151") (name "unconnected-(U4-PG15{slash}U6_CTS{slash}DCMI_D13-Pad132)") (class "Default")
      (node (ref "U4") (pin "132") (pinfunction "PG15/U6_CTS/DCMI_D13_132") (pintype "passive"))
    )
  )
)
